# Balancing_Robot_1_1_FTDI.net
KiCad netlist of a schematic drawn in Altium Designer
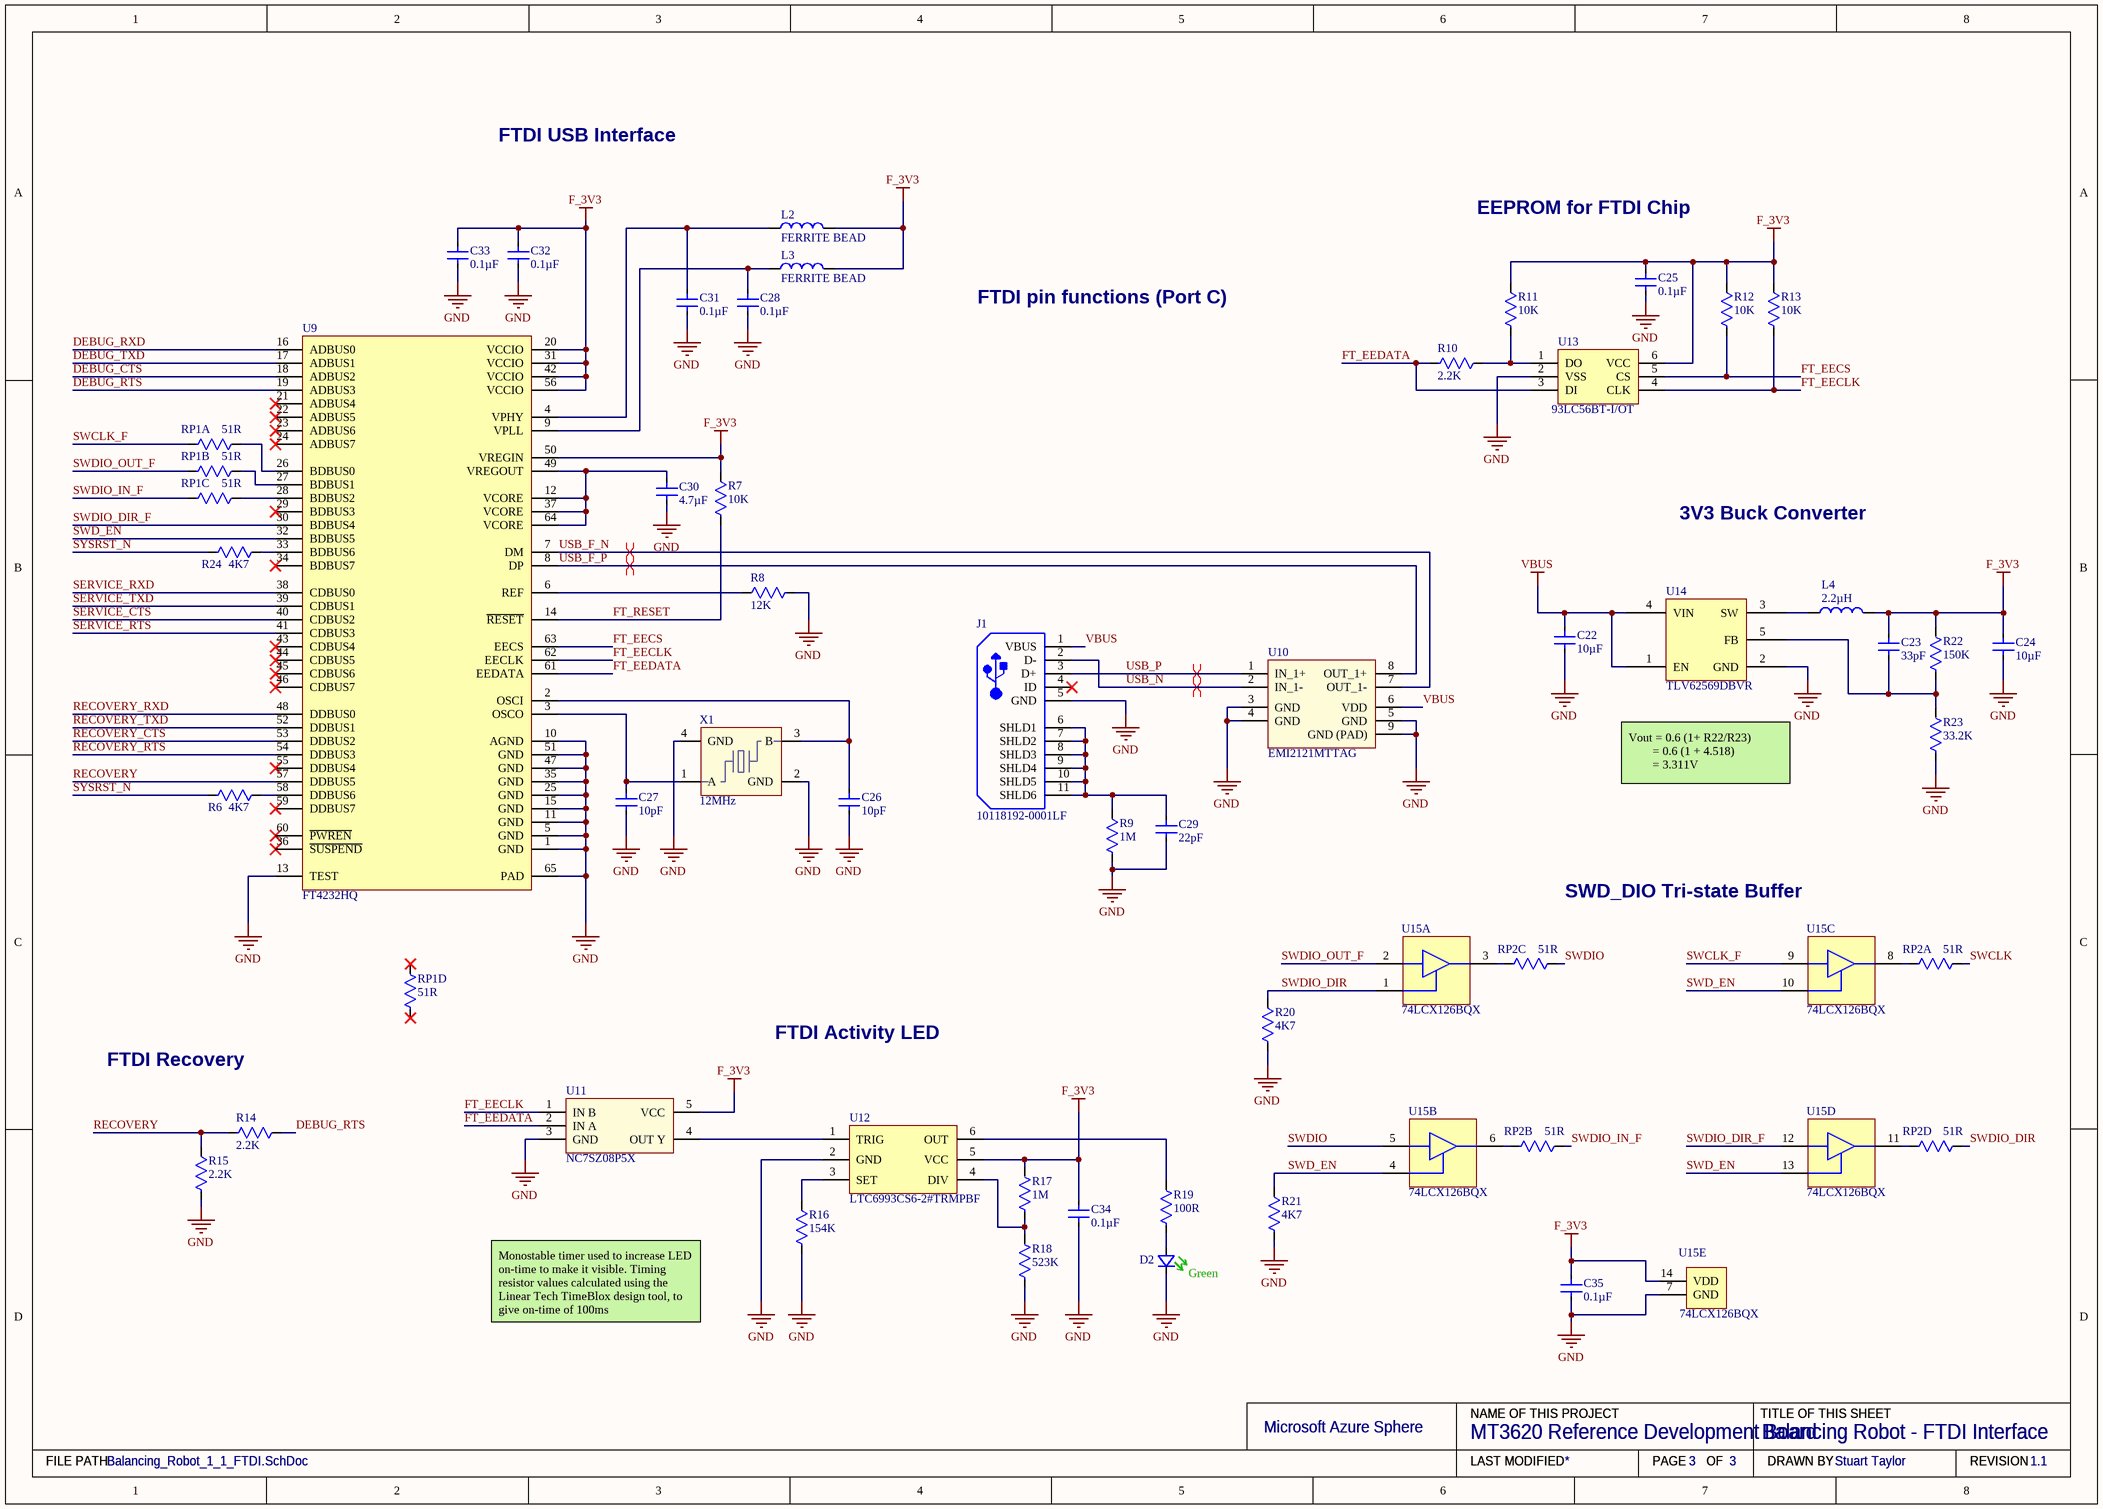
[diagram p0: Balancing_Robot_1_1_FTDI.SchDoc]

(export (version "E")
  (design (tool "Eeschema 10.0.6"))
  (components
    (comp (ref "C22")
      (value "10µF")
      (footprint "CAPC1608-EIA0603-1MM-MED")
      (description "CAP CER 10UF 25V 20% X5R 0603")
      (fields
        (field (name "MANUFACTURER") "TDK Corporation")
        (field (name "MANUFACTURER PART NUMBER") "C1608X5R1E106M080AC")
        (field (name "CAPACITANCE") "10µF")
      )
      (libsource (lib "TDK-Capacitor_C_0603") (part "10µF 0603 X5R 25V"))
    )
    (comp (ref "C23")
      (value "33pF")
      (footprint "CAPC1005-EIA0402 0.55MM MED")
      (description "CAP CER 33PF 50V 5% NP0 0402")
      (fields
        (field (name "MANUFACTURER") "TDK Corporation")
        (field (name "MANUFACTURER PART NUMBER") "C1005C0G1H330J050BA")
        (field (name "CAPACITANCE") "33pF")
      )
      (libsource (lib "TDK_Capacitor_C_0402") (part "33pF 0402 C0G, NP0 50V"))
    )
    (comp (ref "C24")
      (value "10µF")
      (footprint "CAPC1005-EIA0402 0.55MM MED")
      (description "CAP CER 10UF 6.3V 20% X5R 0402")
      (fields
        (field (name "MANUFACTURER") "TDK Corporation")
        (field (name "MANUFACTURER PART NUMBER") "C1005X5R0J106M050BC")
        (field (name "CAPACITANCE") "10µF")
      )
      (libsource (lib "TDK_Capacitor_C_0402") (part "10µF 0402 X5R 6.3V"))
    )
    (comp (ref "C25")
      (value "0.1µF")
      (footprint "CAPC1005-EIA0402 0.55MM MED")
      (description "CAP CER 0.1UF 50V 10% X7R 0402")
      (fields
        (field (name "MANUFACTURER") "TDK Corporation")
        (field (name "MANUFACTURER PART NUMBER") "C1005X7R1H104K050BB")
        (field (name "CAPACITANCE") "0.1µF")
      )
      (libsource (lib "TDK_Capacitor_C_0402") (part "0.1µF 0402 X7R 50V"))
    )
    (comp (ref "C26")
      (value "10pF")
      (footprint "CAPC1005-EIA0402 0.55MM MED")
      (description "CAP CER 10PF 50V NP0 0402")
      (fields
        (field (name "MANUFACTURER") "TDK Corporation")
        (field (name "MANUFACTURER PART NUMBER") "C1005C0G1H100D050BA")
        (field (name "CAPACITANCE") "10pF")
      )
      (libsource (lib "TDK_Capacitor_C_0402") (part "10pF 0402 C0G, NP0 50V"))
    )
    (comp (ref "C27")
      (value "10pF")
      (footprint "CAPC1005-EIA0402 0.55MM MED")
      (description "CAP CER 10PF 50V NP0 0402")
      (fields
        (field (name "MANUFACTURER") "TDK Corporation")
        (field (name "MANUFACTURER PART NUMBER") "C1005C0G1H100D050BA")
        (field (name "CAPACITANCE") "10pF")
      )
      (libsource (lib "TDK_Capacitor_C_0402") (part "10pF 0402 C0G, NP0 50V"))
    )
    (comp (ref "C28")
      (value "0.1µF")
      (footprint "CAPC1005-EIA0402 0.55MM MED")
      (description "CAP CER 0.1UF 50V 10% X7R 0402")
      (fields
        (field (name "MANUFACTURER") "TDK Corporation")
        (field (name "MANUFACTURER PART NUMBER") "C1005X7R1H104K050BB")
        (field (name "CAPACITANCE") "0.1µF")
      )
      (libsource (lib "TDK_Capacitor_C_0402") (part "0.1µF 0402 X7R 50V"))
    )
    (comp (ref "C29")
      (value "22pF")
      (footprint "CAPC1005-EIA0402 0.55MM MED")
      (description "CAP CER 22PF 50V 5% NP0 0402")
      (fields
        (field (name "MANUFACTURER") "TDK Corporation")
        (field (name "MANUFACTURER PART NUMBER") "C1005C0G1H220J050BA")
        (field (name "CAPACITANCE") "22pF")
      )
      (libsource (lib "TDK_Capacitor_C_0402") (part "22pF 0402 C0G, NP0 50V"))
    )
    (comp (ref "C30")
      (value "4.7µF")
      (footprint "CAPC1005-EIA0402 0.55MM MED")
      (description "CAP CER 4.7UF 10V 10% X5R 0402")
      (fields
        (field (name "MANUFACTURER") "TDK Corporation")
        (field (name "MANUFACTURER PART NUMBER") "C1005X5R1A475K050BC")
        (field (name "CAPACITANCE") "4.7µF")
      )
      (libsource (lib "TDK_Capacitor_C_0402") (part "4.7µF 0402 X5R 10V"))
    )
    (comp (ref "C31")
      (value "0.1µF")
      (footprint "CAPC1005-EIA0402 0.55MM MED")
      (description "CAP CER 0.1UF 50V 10% X7R 0402")
      (fields
        (field (name "MANUFACTURER") "TDK Corporation")
        (field (name "MANUFACTURER PART NUMBER") "C1005X7R1H104K050BB")
        (field (name "CAPACITANCE") "0.1µF")
      )
      (libsource (lib "TDK_Capacitor_C_0402") (part "0.1µF 0402 X7R 50V"))
    )
    (comp (ref "C32")
      (value "0.1µF")
      (footprint "CAPC1005-EIA0402 0.55MM MED")
      (description "CAP CER 0.1UF 50V 10% X7R 0402")
      (fields
        (field (name "MANUFACTURER") "TDK Corporation")
        (field (name "MANUFACTURER PART NUMBER") "C1005X7R1H104K050BB")
        (field (name "CAPACITANCE") "0.1µF")
      )
      (libsource (lib "TDK_Capacitor_C_0402") (part "0.1µF 0402 X7R 50V"))
    )
    (comp (ref "C33")
      (value "0.1µF")
      (footprint "CAPC1005-EIA0402 0.55MM MED")
      (description "CAP CER 0.1UF 50V 10% X7R 0402")
      (fields
        (field (name "MANUFACTURER") "TDK Corporation")
        (field (name "MANUFACTURER PART NUMBER") "C1005X7R1H104K050BB")
        (field (name "CAPACITANCE") "0.1µF")
      )
      (libsource (lib "TDK_Capacitor_C_0402") (part "0.1µF 0402 X7R 50V"))
    )
    (comp (ref "C34")
      (value "0.1µF")
      (footprint "CAPC1005-EIA0402 0.55MM MED")
      (description "CAP CER 0.1UF 50V 10% X7R 0402")
      (fields
        (field (name "MANUFACTURER") "TDK Corporation")
        (field (name "MANUFACTURER PART NUMBER") "C1005X7R1H104K050BB")
        (field (name "CAPACITANCE") "0.1µF")
      )
      (libsource (lib "TDK_Capacitor_C_0402") (part "0.1µF 0402 X7R 50V"))
    )
    (comp (ref "C35")
      (value "0.1µF")
      (footprint "CAPC1005-EIA0402 0.55MM MED")
      (description "CAP CER 0.1UF 50V 10% X7R 0402")
      (fields
        (field (name "MANUFACTURER") "TDK Corporation")
        (field (name "MANUFACTURER PART NUMBER") "C1005X7R1H104K050BB")
        (field (name "CAPACITANCE") "0.1µF")
      )
      (libsource (lib "TDK_Capacitor_C_0402") (part "0.1µF 0402 X7R 50V"))
    )
    (comp (ref "D2")
      (value "Green LED")
      (footprint "Rohm SML-D12 Green")
      (description "1.6 x 0.8 x 0.55mm (0603) LED 560nm Green")
      (fields
        (field (name "MANUFACTURER") "Rohm Semiconductor")
        (field (name "MANUFACTURER PART NUMBER") "SML-D12P8WT86")
        (field (name "COLOUR") "Green")
      )
      (libsource (lib "Rohm") (part "SML-D12P"))
    )
    (comp (ref "J1")
      (value "Amphenol FCI 10118192-0001LF")
      (footprint "FCI-10118192-0001LF-5_V")
      (description "USB micro B with no TH anchors")
      (fields
        (field (name "MANUFACTURER") "Amphenol FCI")
        (field (name "MANUFACTURER PART NUMBER") "10118192-0001LF")
        (field (name "CREATED BY") "HUGHWI")
      )
      (libsource (lib "Amphenol") (part "Amphenol FCI 10118192-0001LF"))
    )
    (comp (ref "L2")
      (value "FERRITE BEAD")
      (footprint "CAPC1005-EIA0402 0.55MM MED")
      (description "FERRITE BEAD 120 OHM 0402 1LN")
      (fields
        (field (name "MANUFACTURER") "Murata Electronics North America")
        (field (name "MANUFACTURER PART NUMBER") "BLM15PD121SN1D")
      )
      (libsource (lib "Murata") (part "BLM15PD121SN1D"))
    )
    (comp (ref "L3")
      (value "FERRITE BEAD")
      (footprint "CAPC1005-EIA0402 0.55MM MED")
      (description "FERRITE BEAD 120 OHM 0402 1LN")
      (fields
        (field (name "MANUFACTURER") "Murata Electronics North America")
        (field (name "MANUFACTURER PART NUMBER") "BLM15PD121SN1D")
      )
      (libsource (lib "Murata") (part "BLM15PD121SN1D"))
    )
    (comp (ref "L4")
      (value "2.2µH")
      (footprint "NR3015T2R2M")
      (description "FIXED IND 2.2UH 1.5A 72 MOHM SMD")
      (fields
        (field (name "MANUFACTURER") "Taiyo Yuden")
        (field (name "MANUFACTURER PART NUMBER") "NR3015T2R2M")
      )
      (libsource (lib "TaiyoYuden ") (part "NR3015T2R2M"))
    )
    (comp (ref "R6")
      (value "4K7")
      (footprint "RES 0402 MEDIUM DENSITY")
      (description "RES 4.7K OHM 1/10W 1% 0402 SMD")
      (fields
        (field (name "MANUFACTURER") "Panasonic Electronic Components")
        (field (name "MANUFACTURER PART NUMBER") "ERJ-2RKF4701X")
        (field (name "RESISTANCE (OHMS)") "4K7")
      )
      (libsource (lib "Panasonic_Resistor_ERJ2R") (part "4.7K"))
    )
    (comp (ref "R7")
      (value "10K")
      (footprint "RES 0402 MEDIUM DENSITY")
      (description "RES 10K OHM 1/10W 1% 0402 SMD")
      (fields
        (field (name "MANUFACTURER") "Panasonic Electronic Components")
        (field (name "MANUFACTURER PART NUMBER") "ERJ-2RKF1002X")
        (field (name "RESISTANCE (OHMS)") "10K")
      )
      (libsource (lib "Panasonic_Resistor_ERJ2R") (part "10K"))
    )
    (comp (ref "R8")
      (value "12K")
      (footprint "RES 0402 MEDIUM DENSITY")
      (description "RES 12K OHM 1/10W 1% 0402 SMD")
      (fields
        (field (name "MANUFACTURER") "Panasonic Electronic Components")
        (field (name "MANUFACTURER PART NUMBER") "ERJ-2RKF1202X")
        (field (name "RESISTANCE (OHMS)") "12K")
      )
      (libsource (lib "Panasonic_Resistor_ERJ2R") (part "12K"))
    )
    (comp (ref "R9")
      (value "1M")
      (footprint "RES 0402 MEDIUM DENSITY")
      (description "RES 1M OHM 1/10W 1% 0402 SMD")
      (fields
        (field (name "MANUFACTURER") "Panasonic Electronic Components")
        (field (name "MANUFACTURER PART NUMBER") "ERJ-2RKF1004X")
        (field (name "RESISTANCE (OHMS)") "1M")
      )
      (libsource (lib "Panasonic_Resistor_ERJ2R") (part "1M"))
    )
    (comp (ref "R10")
      (value "2.2K")
      (footprint "RES 0402 MEDIUM DENSITY")
      (description "RES 2.2K OHM 1/10W 1% 0402 SMD")
      (fields
        (field (name "MANUFACTURER") "Panasonic Electronic Components")
        (field (name "MANUFACTURER PART NUMBER") "ERJ-2RKF2201X")
        (field (name "RESISTANCE (OHMS)") "2.2K")
      )
      (libsource (lib "Panasonic_Resistor_ERJ2R") (part "2.2K"))
    )
    (comp (ref "R11")
      (value "10K")
      (footprint "RES 0402 MEDIUM DENSITY")
      (description "RES 10K OHM 1/10W 1% 0402 SMD")
      (fields
        (field (name "MANUFACTURER") "Panasonic Electronic Components")
        (field (name "MANUFACTURER PART NUMBER") "ERJ-2RKF1002X")
        (field (name "RESISTANCE (OHMS)") "10K")
      )
      (libsource (lib "Panasonic_Resistor_ERJ2R") (part "10K"))
    )
    (comp (ref "R12")
      (value "10K")
      (footprint "RES 0402 MEDIUM DENSITY")
      (description "RES 10K OHM 1/10W 1% 0402 SMD")
      (fields
        (field (name "MANUFACTURER") "Panasonic Electronic Components")
        (field (name "MANUFACTURER PART NUMBER") "ERJ-2RKF1002X")
        (field (name "RESISTANCE (OHMS)") "10K")
      )
      (libsource (lib "Panasonic_Resistor_ERJ2R") (part "10K"))
    )
    (comp (ref "R13")
      (value "10K")
      (footprint "RES 0402 MEDIUM DENSITY")
      (description "RES 10K OHM 1/10W 1% 0402 SMD")
      (fields
        (field (name "MANUFACTURER") "Panasonic Electronic Components")
        (field (name "MANUFACTURER PART NUMBER") "ERJ-2RKF1002X")
        (field (name "RESISTANCE (OHMS)") "10K")
      )
      (libsource (lib "Panasonic_Resistor_ERJ2R") (part "10K"))
    )
    (comp (ref "R14")
      (value "2.2K")
      (footprint "RES 0402 MEDIUM DENSITY")
      (description "RES 2.2K OHM 1/10W 1% 0402 SMD")
      (fields
        (field (name "MANUFACTURER") "Panasonic Electronic Components")
        (field (name "MANUFACTURER PART NUMBER") "ERJ-2RKF2201X")
        (field (name "RESISTANCE (OHMS)") "2.2K")
      )
      (libsource (lib "Panasonic_Resistor_ERJ2R") (part "2.2K"))
    )
    (comp (ref "R15")
      (value "2.2K")
      (footprint "RES 0402 MEDIUM DENSITY")
      (description "RES 2.2K OHM 1/10W 1% 0402 SMD")
      (fields
        (field (name "MANUFACTURER") "Panasonic Electronic Components")
        (field (name "MANUFACTURER PART NUMBER") "ERJ-2RKF2201X")
        (field (name "RESISTANCE (OHMS)") "2.2K")
      )
      (libsource (lib "Panasonic_Resistor_ERJ2R") (part "2.2K"))
    )
    (comp (ref "R16")
      (value "154K")
      (footprint "RES 0402 MEDIUM DENSITY")
      (description "RES 154K OHM 1/10W 1% 0402 SMD")
      (fields
        (field (name "MANUFACTURER") "Panasonic Electronic Components")
        (field (name "MANUFACTURER PART NUMBER") "ERJ-2RKF1543X")
        (field (name "RESISTANCE (OHMS)") "154K")
      )
      (libsource (lib "Panasonic_Resistor_ERJ2R") (part "154K"))
    )
    (comp (ref "R17")
      (value "1M")
      (footprint "RES 0402 MEDIUM DENSITY")
      (description "RES 1M OHM 1/10W 1% 0402 SMD")
      (fields
        (field (name "MANUFACTURER") "Panasonic Electronic Components")
        (field (name "MANUFACTURER PART NUMBER") "ERJ-2RKF1004X")
        (field (name "RESISTANCE (OHMS)") "1M")
      )
      (libsource (lib "Panasonic_Resistor_ERJ2R") (part "1M"))
    )
    (comp (ref "R18")
      (value "523K")
      (footprint "RES 0402 MEDIUM DENSITY")
      (description "RES 523K OHM 1/10W 1% 0402 SMD")
      (fields
        (field (name "MANUFACTURER") "Panasonic Electronic Components")
        (field (name "MANUFACTURER PART NUMBER") "ERJ-2RKF5233X")
        (field (name "RESISTANCE (OHMS)") "523K")
      )
      (libsource (lib "Panasonic_Resistor_ERJ2R") (part "523K"))
    )
    (comp (ref "R19")
      (value "100R")
      (footprint "RES 0402 MEDIUM DENSITY")
      (description "RES 100 OHM 1/10W 1% 0402 SMD")
      (fields
        (field (name "MANUFACTURER") "Panasonic Electronic Components")
        (field (name "MANUFACTURER PART NUMBER") "ERJ-2RKF1000X")
        (field (name "RESISTANCE (OHMS)") "100R")
      )
      (libsource (lib "Panasonic_Resistor_ERJ2R") (part "100R"))
    )
    (comp (ref "R20")
      (value "4K7")
      (footprint "RES 0402 MEDIUM DENSITY")
      (description "RES 4.7K OHM 1/10W 1% 0402 SMD")
      (fields
        (field (name "MANUFACTURER") "Panasonic Electronic Components")
        (field (name "MANUFACTURER PART NUMBER") "ERJ-2RKF4701X")
        (field (name "RESISTANCE (OHMS)") "4K7")
      )
      (libsource (lib "Panasonic_Resistor_ERJ2R") (part "4.7K"))
    )
    (comp (ref "R21")
      (value "4K7")
      (footprint "RES 0402 MEDIUM DENSITY")
      (description "RES 4.7K OHM 1/10W 1% 0402 SMD")
      (fields
        (field (name "MANUFACTURER") "Panasonic Electronic Components")
        (field (name "MANUFACTURER PART NUMBER") "ERJ-2RKF4701X")
        (field (name "RESISTANCE (OHMS)") "4K7")
      )
      (libsource (lib "Panasonic_Resistor_ERJ2R") (part "4.7K"))
    )
    (comp (ref "R22")
      (value "150K")
      (footprint "RES 0402 MEDIUM DENSITY")
      (description "RES 150K OHM 1/10W 1% 0402 SMD")
      (fields
        (field (name "MANUFACTURER") "Panasonic Electronic Components")
        (field (name "MANUFACTURER PART NUMBER") "ERJ-2RKF1503X")
        (field (name "RESISTANCE (OHMS)") "150K")
      )
      (libsource (lib "Panasonic_Resistor_ERJ2R") (part "150K"))
    )
    (comp (ref "R23")
      (value "33.2K")
      (footprint "RES 0402 MEDIUM DENSITY")
      (description "RES 33.2K OHM 1/10W 1% 0402 SMD")
      (fields
        (field (name "MANUFACTURER") "Panasonic Electronic Components")
        (field (name "MANUFACTURER PART NUMBER") "ERJ-2RKF3322X")
        (field (name "RESISTANCE (OHMS)") "33.2K")
      )
      (libsource (lib "Panasonic_Resistor_ERJ2R") (part "33.2K"))
    )
    (comp (ref "R24")
      (value "4K7")
      (footprint "RES 0402 MEDIUM DENSITY")
      (description "RES 4.7K OHM 1/10W 1% 0402 SMD")
      (fields
        (field (name "MANUFACTURER") "Panasonic Electronic Components")
        (field (name "MANUFACTURER PART NUMBER") "ERJ-2RKF4701X")
        (field (name "RESISTANCE (OHMS)") "4K7")
      )
      (libsource (lib "Panasonic_Resistor_ERJ2R") (part "4.7K"))
    )
    (comp (ref "RP1")
      (value "51R")
      (footprint "EXB-N8V")
      (fields
        (field (name "MANUFACTURER") "Panasonic / Panasonic ECG")
        (field (name "MANUFACTURER PART NUMBER") "EXB-N8V510JX")
      )
      (libsource (lib "Panasonic") (part "EXB-N8V510JX"))
    )
    (comp (ref "RP2")
      (value "51R")
      (footprint "EXB-N8V")
      (fields
        (field (name "MANUFACTURER") "Panasonic / Panasonic ECG")
        (field (name "MANUFACTURER PART NUMBER") "EXB-N8V510JX")
      )
      (libsource (lib "Panasonic") (part "EXB-N8V510JX"))
    )
    (comp (ref "U9")
      (value "FT4232HQ")
      (footprint "FTDI_TF4232HQ_64QFN")
      (description "IC USB HS QUAD UART/SYNC 64-QFN")
      (fields
        (field (name "MANUFACTURER") "FTDI, Future Technology Devices International Ltd")
        (field (name "MANUFACTURER PART NUMBER") "FT4232HQ-REEL")
      )
      (libsource (lib "FTDI") (part "FT4232HQ"))
    )
    (comp (ref "U10")
      (value "EMI2121MTTAG")
      (footprint "EMI2121MTTAG")
      (description "IC FILTER COMMON MODE ESD 8WDFN")
      (fields (field (name "MANUFACTURER") "ON Semiconductor"))
      (libsource (lib "OnSemiconductor") (part "EMI2121MTTAG"))
    )
    (comp (ref "U11")
      (value "NC7SZ08P5X")
      (footprint "SC-70-5")
      (description "IC GATE AND 1CH 2-INP SC-70-5")
      (fields (field (name "MANUFACTURER") "Fairchild Semiconductor"))
      (libsource (lib "OnSemiconductor") (part "NC7SZ08P5X"))
    )
    (comp (ref "U12")
      (value "LTC6993CS6-2#TRMPBF")
      (footprint "LTC6993CS6-2#TRMPBF")
      (description "LINEAR TECHNOLOGY - LTC6993CS6-2#TRMPBF - GENERATOR, PULSE, TIMERBLOX, 6SOT-23")
      (fields (field (name "MANUFACTURER") "LINEAR TECHNOLOGY"))
      (libsource (lib "LinearTech") (part "LTC6993CS6-2#TRMPBF"))
    )
    (comp (ref "U13")
      (value "93LC56BT-I/OT")
      (footprint "SOT23-93C56B")
      (description "IC EEPROM 2KBIT 2MHZ SOT23-6")
      (fields (field (name "MANUFACTURER") "Microchip Technology"))
      (libsource (lib "Microchip") (part "93LC56BT-I/OT"))
    )
    (comp (ref "U14")
      (value "TLV62569DBVR")
      (footprint "TI-SOT23-6")
      (description "Variable voltage buck converter")
      (fields (field (name "MANUFACTURER") "Texas Instruments"))
      (libsource (lib "TexasInstruments") (part "TLV62569DBVR"))
    )
    (comp (ref "U15")
      (value "74LCX126BQX")
      (footprint "74LCX126BQX")
      (description "IC BUFFER QUAD LV N-INV 14DQFN")
      (fields (field (name "MANUFACTURER") "Fairchild Semiconductor"))
      (libsource (lib "OnSemiconductor") (part "74LCX126BQX"))
    )
    (comp (ref "X1")
      (value "12MHz")
      (footprint "TXC 8Z")
      (description "CRYSTAL 12.000 MHZ 18PF SMD")
      (fields
        (field (name "MANUFACTURER") "TXC CORPORATION")
        (field (name "MANUFACTURER PART NUMBER") "8Z-12.000MAAJ-T")
        (field (name "FREQUENCY") "12MHz")
      )
      (libsource (lib "crystal") (part "CRYSTAL 12MHz 18pF SMD"))
    )
  )
  (nets
    (net (code "1") (name "/DEBUG_CTS") (class "Default")
      (node (ref "U9") (pin "18") (pinfunction "ADBUS2_18") (pintype "passive"))
    )
    (net (code "2") (name "/DEBUG_RTS") (class "Default")
      (node (ref "R14") (pin "1") (pinfunction "1_1") (pintype "passive"))
      (node (ref "U9") (pin "19") (pinfunction "ADBUS3_19") (pintype "passive"))
    )
    (net (code "3") (name "/DEBUG_RXD") (class "Default")
      (node (ref "U9") (pin "16") (pinfunction "ADBUS0_16") (pintype "passive"))
    )
    (net (code "4") (name "/DEBUG_TXD") (class "Default")
      (node (ref "U9") (pin "17") (pinfunction "ADBUS1_17") (pintype "passive"))
    )
    (net (code "5") (name "/FT_EECLK") (class "Default")
      (node (ref "R13") (pin "2") (pinfunction "2_2") (pintype "passive"))
      (node (ref "U11") (pin "1") (pinfunction "IN_B_1") (pintype "passive"))
      (node (ref "U13") (pin "4") (pinfunction "CLK_4") (pintype "passive"))
      (node (ref "U9") (pin "62") (pinfunction "EECLK_62") (pintype "passive"))
    )
    (net (code "6") (name "/FT_EECS") (class "Default")
      (node (ref "R12") (pin "2") (pinfunction "2_2") (pintype "passive"))
      (node (ref "U13") (pin "5") (pinfunction "CS_5") (pintype "passive"))
      (node (ref "U9") (pin "63") (pinfunction "EECS_63") (pintype "passive"))
    )
    (net (code "7") (name "/FT_EEDATA") (class "Default")
      (node (ref "R10") (pin "2") (pinfunction "2_2") (pintype "passive"))
      (node (ref "U11") (pin "2") (pinfunction "IN_A_2") (pintype "passive"))
      (node (ref "U13") (pin "3") (pinfunction "DI_3") (pintype "passive"))
      (node (ref "U9") (pin "61") (pinfunction "EEDATA_61") (pintype "passive"))
    )
    (net (code "8") (name "/FT_RESET") (class "Default")
      (node (ref "R7") (pin "2") (pinfunction "2_2") (pintype "passive"))
      (node (ref "U9") (pin "14") (pinfunction "~{RESET}_14") (pintype "passive"))
    )
    (net (code "9") (name "/RECOVERY") (class "Default")
      (node (ref "R14") (pin "2") (pinfunction "2_2") (pintype "passive"))
      (node (ref "R15") (pin "1") (pinfunction "1_1") (pintype "passive"))
      (node (ref "U9") (pin "57") (pinfunction "DDBUS5_57") (pintype "passive"))
    )
    (net (code "10") (name "/RECOVERY_CTS") (class "Default")
      (node (ref "U9") (pin "53") (pinfunction "DDBUS2_53") (pintype "passive"))
    )
    (net (code "11") (name "/RECOVERY_RTS") (class "Default")
      (node (ref "U9") (pin "54") (pinfunction "DDBUS3_54") (pintype "passive"))
    )
    (net (code "12") (name "/RECOVERY_RXD") (class "Default")
      (node (ref "U9") (pin "48") (pinfunction "DDBUS0_48") (pintype "passive"))
    )
    (net (code "13") (name "/RECOVERY_TXD") (class "Default")
      (node (ref "U9") (pin "52") (pinfunction "DDBUS1_52") (pintype "passive"))
    )
    (net (code "14") (name "/SERVICE_CTS") (class "Default")
      (node (ref "U9") (pin "40") (pinfunction "CDBUS2_40") (pintype "passive"))
    )
    (net (code "15") (name "/SERVICE_RTS") (class "Default")
      (node (ref "U9") (pin "41") (pinfunction "CDBUS3_41") (pintype "passive"))
    )
    (net (code "16") (name "/SERVICE_RXD") (class "Default")
      (node (ref "U9") (pin "38") (pinfunction "CDBUS0_38") (pintype "passive"))
    )
    (net (code "17") (name "/SERVICE_TXD") (class "Default")
      (node (ref "U9") (pin "39") (pinfunction "CDBUS1_39") (pintype "passive"))
    )
    (net (code "18") (name "/SWCLK") (class "Default")
      (node (ref "RP2") (pin "2") (pinfunction "2_2") (pintype "passive"))
    )
    (net (code "19") (name "/SWCLK_F") (class "Default")
      (node (ref "RP1") (pin "1") (pinfunction "1_1") (pintype "passive"))
      (node (ref "U15") (pin "9") (pinfunction "3A_9") (pintype "passive"))
    )
    (net (code "20") (name "/SWDIO") (class "Default")
      (node (ref "RP2") (pin "6") (pinfunction "6_6") (pintype "passive"))
      (node (ref "U15") (pin "5") (pinfunction "2A_5") (pintype "passive"))
    )
    (net (code "21") (name "/SWDIO_DIR") (class "Default")
      (node (ref "R20") (pin "1") (pinfunction "1_1") (pintype "passive"))
      (node (ref "RP2") (pin "8") (pinfunction "8_8") (pintype "passive"))
      (node (ref "U15") (pin "1") (pinfunction "1OE_1") (pintype "passive"))
    )
    (net (code "22") (name "/SWDIO_DIR_F") (class "Default")
      (node (ref "U15") (pin "12") (pinfunction "4A_12") (pintype "passive"))
      (node (ref "U9") (pin "30") (pinfunction "BDBUS4_30") (pintype "passive"))
    )
    (net (code "23") (name "/SWDIO_IN_F") (class "Default")
      (node (ref "RP1") (pin "5") (pinfunction "5_5") (pintype "passive"))
      (node (ref "RP2") (pin "4") (pinfunction "4_4") (pintype "passive"))
    )
    (net (code "24") (name "/SWDIO_OUT_F") (class "Default")
      (node (ref "RP1") (pin "3") (pinfunction "3_3") (pintype "passive"))
      (node (ref "U15") (pin "2") (pinfunction "1A_2") (pintype "passive"))
    )
    (net (code "25") (name "/SWD_EN") (class "Default")
      (node (ref "R21") (pin "1") (pinfunction "1_1") (pintype "passive"))
      (node (ref "U15") (pin "10") (pinfunction "3OE_10") (pintype "passive"))
      (node (ref "U15") (pin "13") (pinfunction "4OE_13") (pintype "passive"))
      (node (ref "U15") (pin "4") (pinfunction "2OE_4") (pintype "passive"))
      (node (ref "U9") (pin "32") (pinfunction "BDBUS5_32") (pintype "passive"))
    )
    (net (code "26") (name "/SYSRST_N") (class "Default")
      (node (ref "R24") (pin "2") (pinfunction "2_2") (pintype "passive"))
      (node (ref "R6") (pin "2") (pinfunction "2_2") (pintype "passive"))
    )
    (net (code "27") (name "/USB_F_N") (class "Default")
      (node (ref "U10") (pin "7") (pinfunction "OUT_1-_7") (pintype "passive"))
      (node (ref "U9") (pin "7") (pinfunction "DM_7") (pintype "passive"))
    )
    (net (code "28") (name "/USB_F_P") (class "Default")
      (node (ref "U10") (pin "8") (pinfunction "OUT_1+_8") (pintype "passive"))
      (node (ref "U9") (pin "8") (pinfunction "DP_8") (pintype "passive"))
    )
    (net (code "29") (name "/USB_N") (class "Default")
      (node (ref "J1") (pin "2") (pinfunction "D-_2") (pintype "passive"))
      (node (ref "U10") (pin "2") (pinfunction "IN_1-_2") (pintype "passive"))
    )
    (net (code "30") (name "/USB_P") (class "Default")
      (node (ref "J1") (pin "3") (pinfunction "D+_3") (pintype "passive"))
      (node (ref "U10") (pin "1") (pinfunction "IN_1+_1") (pintype "passive"))
    )
    (net (code "31") (name "F_3V3") (class "Default")
      (node (ref "C23") (pin "2") (pinfunction "2_2") (pintype "passive"))
      (node (ref "C24") (pin "2") (pinfunction "2_2") (pintype "passive"))
      (node (ref "C25") (pin "2") (pinfunction "2_2") (pintype "passive"))
      (node (ref "C32") (pin "2") (pinfunction "2_2") (pintype "passive"))
      (node (ref "C33") (pin "2") (pinfunction "2_2") (pintype "passive"))
      (node (ref "C34") (pin "2") (pinfunction "2_2") (pintype "passive"))
      (node (ref "C35") (pin "2") (pinfunction "2_2") (pintype "passive"))
      (node (ref "L2") (pin "2") (pinfunction "2_2") (pintype "passive"))
      (node (ref "L3") (pin "2") (pinfunction "2_2") (pintype "passive"))
      (node (ref "L4") (pin "2") (pinfunction "2_2") (pintype "passive"))
      (node (ref "R11") (pin "1") (pinfunction "1_1") (pintype "passive"))
      (node (ref "R12") (pin "1") (pinfunction "1_1") (pintype "passive"))
      (node (ref "R13") (pin "1") (pinfunction "1_1") (pintype "passive"))
      (node (ref "R17") (pin "1") (pinfunction "1_1") (pintype "passive"))
      (node (ref "R22") (pin "1") (pinfunction "1_1") (pintype "passive"))
      (node (ref "R7") (pin "1") (pinfunction "1_1") (pintype "passive"))
      (node (ref "U11") (pin "5") (pinfunction "VCC_5") (pintype "passive"))
      (node (ref "U12") (pin "5") (pinfunction "VCC_5") (pintype "passive"))
      (node (ref "U13") (pin "6") (pinfunction "VCC_6") (pintype "passive"))
      (node (ref "U15") (pin "14") (pinfunction "VDD_14") (pintype "passive"))
      (node (ref "U9") (pin "20") (pinfunction "VCCIO_20") (pintype "passive"))
      (node (ref "U9") (pin "31") (pinfunction "VCCIO_31") (pintype "passive"))
      (node (ref "U9") (pin "42") (pinfunction "VCCIO_42") (pintype "passive"))
      (node (ref "U9") (pin "50") (pinfunction "VREGIN_50") (pintype "passive"))
      (node (ref "U9") (pin "56") (pinfunction "VCCIO_56") (pintype "passive"))
    )
    (net (code "32") (name "GND") (class "Default")
      (node (ref "C22") (pin "1") (pinfunction "1_1") (pintype "passive"))
      (node (ref "C24") (pin "1") (pinfunction "1_1") (pintype "passive"))
      (node (ref "C25") (pin "1") (pinfunction "1_1") (pintype "passive"))
      (node (ref "C26") (pin "1") (pinfunction "1_1") (pintype "passive"))
      (node (ref "C27") (pin "1") (pinfunction "1_1") (pintype "passive"))
      (node (ref "C28") (pin "1") (pinfunction "1_1") (pintype "passive"))
      (node (ref "C29") (pin "1") (pinfunction "1_1") (pintype "passive"))
      (node (ref "C30") (pin "1") (pinfunction "1_1") (pintype "passive"))
      (node (ref "C31") (pin "1") (pinfunction "1_1") (pintype "passive"))
      (node (ref "C32") (pin "1") (pinfunction "1_1") (pintype "passive"))
      (node (ref "C33") (pin "1") (pinfunction "1_1") (pintype "passive"))
      (node (ref "C34") (pin "1") (pinfunction "1_1") (pintype "passive"))
      (node (ref "C35") (pin "1") (pinfunction "1_1") (pintype "passive"))
      (node (ref "D2") (pin "1") (pinfunction "K_1") (pintype "passive"))
      (node (ref "J1") (pin "5") (pinfunction "GND_5") (pintype "passive"))
      (node (ref "R15") (pin "2") (pinfunction "2_2") (pintype "passive"))
      (node (ref "R16") (pin "2") (pinfunction "2_2") (pintype "passive"))
      (node (ref "R18") (pin "2") (pinfunction "2_2") (pintype "passive"))
      (node (ref "R20") (pin "2") (pinfunction "2_2") (pintype "passive"))
      (node (ref "R21") (pin "2") (pinfunction "2_2") (pintype "passive"))
      (node (ref "R23") (pin "2") (pinfunction "2_2") (pintype "passive"))
      (node (ref "R8") (pin "2") (pinfunction "2_2") (pintype "passive"))
      (node (ref "R9") (pin "2") (pinfunction "2_2") (pintype "passive"))
      (node (ref "U10") (pin "3") (pinfunction "GND_3") (pintype "passive"))
      (node (ref "U10") (pin "4") (pinfunction "GND_4") (pintype "passive"))
      (node (ref "U10") (pin "5") (pinfunction "GND_5") (pintype "passive"))
      (node (ref "U10") (pin "9") (pinfunction "GND_(PAD)_9") (pintype "passive"))
      (node (ref "U11") (pin "3") (pinfunction "GND_3") (pintype "passive"))
      (node (ref "U12") (pin "2") (pinfunction "GND_2") (pintype "passive"))
      (node (ref "U13") (pin "2") (pinfunction "VSS_2") (pintype "passive"))
      (node (ref "U14") (pin "2") (pinfunction "GND_2") (pintype "passive"))
      (node (ref "U15") (pin "7") (pinfunction "GND_7") (pintype "passive"))
      (node (ref "U9") (pin "1") (pinfunction "GND_1") (pintype "passive"))
      (node (ref "U9") (pin "10") (pinfunction "AGND_10") (pintype "passive"))
      (node (ref "U9") (pin "11") (pinfunction "GND_11") (pintype "passive"))
      (node (ref "U9") (pin "13") (pinfunction "TEST_13") (pintype "passive"))
      (node (ref "U9") (pin "15") (pinfunction "GND_15") (pintype "passive"))
      (node (ref "U9") (pin "25") (pinfunction "GND_25") (pintype "passive"))
      (node (ref "U9") (pin "35") (pinfunction "GND_35") (pintype "passive"))
      (node (ref "U9") (pin "47") (pinfunction "GND_47") (pintype "passive"))
      (node (ref "U9") (pin "5") (pinfunction "GND_5") (pintype "passive"))
      (node (ref "U9") (pin "51") (pinfunction "GND_51") (pintype "passive"))
      (node (ref "U9") (pin "65") (pinfunction "PAD_65") (pintype "passive"))
      (node (ref "X1") (pin "2") (pinfunction "GND_2") (pintype "passive"))
      (node (ref "X1") (pin "4") (pinfunction "GND_4") (pintype "passive"))
    )
    (net (code "33") (name "Net-(D2-A)") (class "Default")
      (node (ref "D2") (pin "2") (pinfunction "A_2") (pintype "passive"))
      (node (ref "R19") (pin "2") (pinfunction "2_2") (pintype "passive"))
    )
    (net (code "34") (name "Net-(J1-SHLD1)") (class "Default")
      (node (ref "C29") (pin "2") (pinfunction "2_2") (pintype "passive"))
      (node (ref "J1") (pin "10") (pinfunction "SHLD5_10") (pintype "passive"))
      (node (ref "J1") (pin "11") (pinfunction "SHLD6_11") (pintype "passive"))
      (node (ref "J1") (pin "6") (pinfunction "SHLD1_6") (pintype "passive"))
      (node (ref "J1") (pin "7") (pinfunction "SHLD2_7") (pintype "passive"))
      (node (ref "J1") (pin "8") (pinfunction "SHLD3_8") (pintype "passive"))
      (node (ref "J1") (pin "9") (pinfunction "SHLD4_9") (pintype "passive"))
      (node (ref "R9") (pin "1") (pinfunction "1_1") (pintype "passive"))
    )
    (net (code "35") (name "Net-(U9-BDBUS0)") (class "Default")
      (node (ref "RP1") (pin "2") (pinfunction "2_2") (pintype "passive"))
      (node (ref "U9") (pin "26") (pinfunction "BDBUS0_26") (pintype "passive"))
    )
    (net (code "36") (name "Net-(U9-BDBUS1)") (class "Default")
      (node (ref "RP1") (pin "4") (pinfunction "4_4") (pintype "passive"))
      (node (ref "U9") (pin "27") (pinfunction "BDBUS1_27") (pintype "passive"))
    )
    (net (code "37") (name "Net-(U9-BDBUS2)") (class "Default")
      (node (ref "RP1") (pin "6") (pinfunction "6_6") (pintype "passive"))
      (node (ref "U9") (pin "28") (pinfunction "BDBUS2_28") (pintype "passive"))
    )
    (net (code "38") (name "Net-(U9-BDBUS6)") (class "Default")
      (node (ref "R24") (pin "1") (pinfunction "1_1") (pintype "passive"))
      (node (ref "U9") (pin "33") (pinfunction "BDBUS6_33") (pintype "passive"))
    )
    (net (code "39") (name "Net-(U9-DDBUS6)") (class "Default")
      (node (ref "R6") (pin "1") (pinfunction "1_1") (pintype "passive"))
      (node (ref "U9") (pin "58") (pinfunction "DDBUS6_58") (pintype "passive"))
    )
    (net (code "40") (name "Net-(U9-OSCI)") (class "Default")
      (node (ref "C26") (pin "2") (pinfunction "2_2") (pintype "passive"))
      (node (ref "U9") (pin "2") (pinfunction "OSCI_2") (pintype "passive"))
      (node (ref "X1") (pin "3") (pinfunction "B_3") (pintype "passive"))
    )
    (net (code "41") (name "Net-(U9-OSCO)") (class "Default")
      (node (ref "C27") (pin "2") (pinfunction "2_2") (pintype "passive"))
      (node (ref "U9") (pin "3") (pinfunction "OSCO_3") (pintype "passive"))
      (node (ref "X1") (pin "1") (pinfunction "A_1") (pintype "passive"))
    )
    (net (code "42") (name "Net-(U9-REF)") (class "Default")
      (node (ref "R8") (pin "1") (pinfunction "1_1") (pintype "passive"))
      (node (ref "U9") (pin "6") (pinfunction "REF_6") (pintype "passive"))
    )
    (net (code "43") (name "Net-(U9-VPHY)") (class "Default")
      (node (ref "C31") (pin "2") (pinfunction "2_2") (pintype "passive"))
      (node (ref "L2") (pin "1") (pinfunction "1_1") (pintype "passive"))
      (node (ref "U9") (pin "4") (pinfunction "VPHY_4") (pintype "passive"))
    )
    (net (code "44") (name "Net-(U9-VPLL)") (class "Default")
      (node (ref "C28") (pin "2") (pinfunction "2_2") (pintype "passive"))
      (node (ref "L3") (pin "1") (pinfunction "1_1") (pintype "passive"))
      (node (ref "U9") (pin "9") (pinfunction "VPLL_9") (pintype "passive"))
    )
    (net (code "45") (name "Net-(U9-VREGOUT)") (class "Default")
      (node (ref "C30") (pin "2") (pinfunction "2_2") (pintype "passive"))
      (node (ref "U9") (pin "12") (pinfunction "VCORE_12") (pintype "passive"))
      (node (ref "U9") (pin "37") (pinfunction "VCORE_37") (pintype "passive"))
      (node (ref "U9") (pin "49") (pinfunction "VREGOUT_49") (pintype "passive"))
      (node (ref "U9") (pin "64") (pinfunction "VCORE_64") (pintype "passive"))
    )
    (net (code "46") (name "Net-(U11-OUT_Y)") (class "Default")
      (node (ref "U11") (pin "4") (pinfunction "OUT_Y_4") (pintype "passive"))
      (node (ref "U12") (pin "1") (pinfunction "TRIG_1") (pintype "passive"))
    )
    (net (code "47") (name "Net-(U12-DIV)") (class "Default")
      (node (ref "R17") (pin "2") (pinfunction "2_2") (pintype "passive"))
      (node (ref "R18") (pin "1") (pinfunction "1_1") (pintype "passive"))
      (node (ref "U12") (pin "4") (pinfunction "DIV_4") (pintype "passive"))
    )
    (net (code "48") (name "Net-(U12-OUT)") (class "Default")
      (node (ref "R19") (pin "1") (pinfunction "1_1") (pintype "passive"))
      (node (ref "U12") (pin "6") (pinfunction "OUT_6") (pintype "passive"))
    )
    (net (code "49") (name "Net-(U12-SET)") (class "Default")
      (node (ref "R16") (pin "1") (pinfunction "1_1") (pintype "passive"))
      (node (ref "U12") (pin "3") (pinfunction "SET_3") (pintype "passive"))
    )
    (net (code "50") (name "Net-(U13-DO)") (class "Default")
      (node (ref "R10") (pin "1") (pinfunction "1_1") (pintype "passive"))
      (node (ref "R11") (pin "2") (pinfunction "2_2") (pintype "passive"))
      (node (ref "U13") (pin "1") (pinfunction "DO_1") (pintype "passive"))
    )
    (net (code "51") (name "Net-(U14-FB)") (class "Default")
      (node (ref "C23") (pin "1") (pinfunction "1_1") (pintype "passive"))
      (node (ref "R22") (pin "2") (pinfunction "2_2") (pintype "passive"))
      (node (ref "R23") (pin "1") (pinfunction "1_1") (pintype "passive"))
      (node (ref "U14") (pin "5") (pinfunction "FB_5") (pintype "passive"))
    )
    (net (code "52") (name "Net-(U14-SW)") (class "Default")
      (node (ref "L4") (pin "1") (pinfunction "1_1") (pintype "passive"))
      (node (ref "U14") (pin "3") (pinfunction "SW_3") (pintype "passive"))
    )
    (net (code "53") (name "Net-(U15A-1Y)") (class "Default")
      (node (ref "RP2") (pin "5") (pinfunction "5_5") (pintype "passive"))
      (node (ref "U15") (pin "3") (pinfunction "1Y_3") (pintype "passive"))
    )
    (net (code "54") (name "Net-(U15B-2Y)") (class "Default")
      (node (ref "RP2") (pin "3") (pinfunction "3_3") (pintype "passive"))
      (node (ref "U15") (pin "6") (pinfunction "2Y_6") (pintype "passive"))
    )
    (net (code "55") (name "Net-(U15C-3Y)") (class "Default")
      (node (ref "RP2") (pin "1") (pinfunction "1_1") (pintype "passive"))
      (node (ref "U15") (pin "8") (pinfunction "3Y_8") (pintype "passive"))
    )
    (net (code "56") (name "Net-(U15D-4Y)") (class "Default")
      (node (ref "RP2") (pin "7") (pinfunction "7_7") (pintype "passive"))
      (node (ref "U15") (pin "11") (pinfunction "4Y_11") (pintype "passive"))
    )
    (net (code "57") (name "VBUS") (class "Default")
      (node (ref "C22") (pin "2") (pinfunction "2_2") (pintype "passive"))
      (node (ref "J1") (pin "1") (pinfunction "VBUS_1") (pintype "passive"))
      (node (ref "U10") (pin "6") (pinfunction "VDD_6") (pintype "passive"))
      (node (ref "U14") (pin "1") (pinfunction "EN_1") (pintype "passive"))
      (node (ref "U14") (pin "4") (pinfunction "VIN_4") (pintype "passive"))
    )
    (net (code "58") (name "unconnected-(J1-ID-Pad4)") (class "Default")
      (node (ref "J1") (pin "4") (pinfunction "ID_4") (pintype "passive+no_connect"))
    )
    (net (code "59") (name "unconnected-(RP1-Pad7)") (class "Default")
      (node (ref "RP1") (pin "7") (pinfunction "7_7") (pintype "passive+no_connect"))
    )
    (net (code "60") (name "unconnected-(RP1-Pad8)") (class "Default")
      (node (ref "RP1") (pin "8") (pinfunction "8_8") (pintype "passive+no_connect"))
    )
    (net (code "61") (name "unconnected-(U9-ADBUS4-Pad21)") (class "Default")
      (node (ref "U9") (pin "21") (pinfunction "ADBUS4_21") (pintype "passive+no_connect"))
    )
    (net (code "62") (name "unconnected-(U9-ADBUS5-Pad22)") (class "Default")
      (node (ref "U9") (pin "22") (pinfunction "ADBUS5_22") (pintype "passive+no_connect"))
    )
    (net (code "63") (name "unconnected-(U9-ADBUS6-Pad23)") (class "Default")
      (node (ref "U9") (pin "23") (pinfunction "ADBUS6_23") (pintype "passive+no_connect"))
    )
    (net (code "64") (name "unconnected-(U9-ADBUS7-Pad24)") (class "Default")
      (node (ref "U9") (pin "24") (pinfunction "ADBUS7_24") (pintype "passive+no_connect"))
    )
    (net (code "65") (name "unconnected-(U9-BDBUS3-Pad29)") (class "Default")
      (node (ref "U9") (pin "29") (pinfunction "BDBUS3_29") (pintype "passive+no_connect"))
    )
    (net (code "66") (name "unconnected-(U9-BDBUS7-Pad34)") (class "Default")
      (node (ref "U9") (pin "34") (pinfunction "BDBUS7_34") (pintype "passive+no_connect"))
    )
    (net (code "67") (name "unconnected-(U9-CDBUS4-Pad43)") (class "Default")
      (node (ref "U9") (pin "43") (pinfunction "CDBUS4_43") (pintype "passive+no_connect"))
    )
    (net (code "68") (name "unconnected-(U9-CDBUS5-Pad44)") (class "Default")
      (node (ref "U9") (pin "44") (pinfunction "CDBUS5_44") (pintype "passive+no_connect"))
    )
    (net (code "69") (name "unconnected-(U9-CDBUS6-Pad45)") (class "Default")
      (node (ref "U9") (pin "45") (pinfunction "CDBUS6_45") (pintype "passive+no_connect"))
    )
    (net (code "70") (name "unconnected-(U9-CDBUS7-Pad46)") (class "Default")
      (node (ref "U9") (pin "46") (pinfunction "CDBUS7_46") (pintype "passive+no_connect"))
    )
    (net (code "71") (name "unconnected-(U9-DDBUS4-Pad55)") (class "Default")
      (node (ref "U9") (pin "55") (pinfunction "DDBUS4_55") (pintype "passive+no_connect"))
    )
    (net (code "72") (name "unconnected-(U9-DDBUS7-Pad59)") (class "Default")
      (node (ref "U9") (pin "59") (pinfunction "DDBUS7_59") (pintype "passive+no_connect"))
    )
    (net (code "73") (name "unconnected-(U9-~{PWREN}-Pad60)") (class "Default")
      (node (ref "U9") (pin "60") (pinfunction "~{PWREN}_60") (pintype "passive+no_connect"))
    )
    (net (code "74") (name "unconnected-(U9-~{SUSPEND}-Pad36)") (class "Default")
      (node (ref "U9") (pin "36") (pinfunction "~{SUSPEND}_36") (pintype "passive+no_connect"))
    )
  )
)
